# SK3000v1_-_3_FINAL.net
KiCad netlist of a schematic drawn in EAGLE
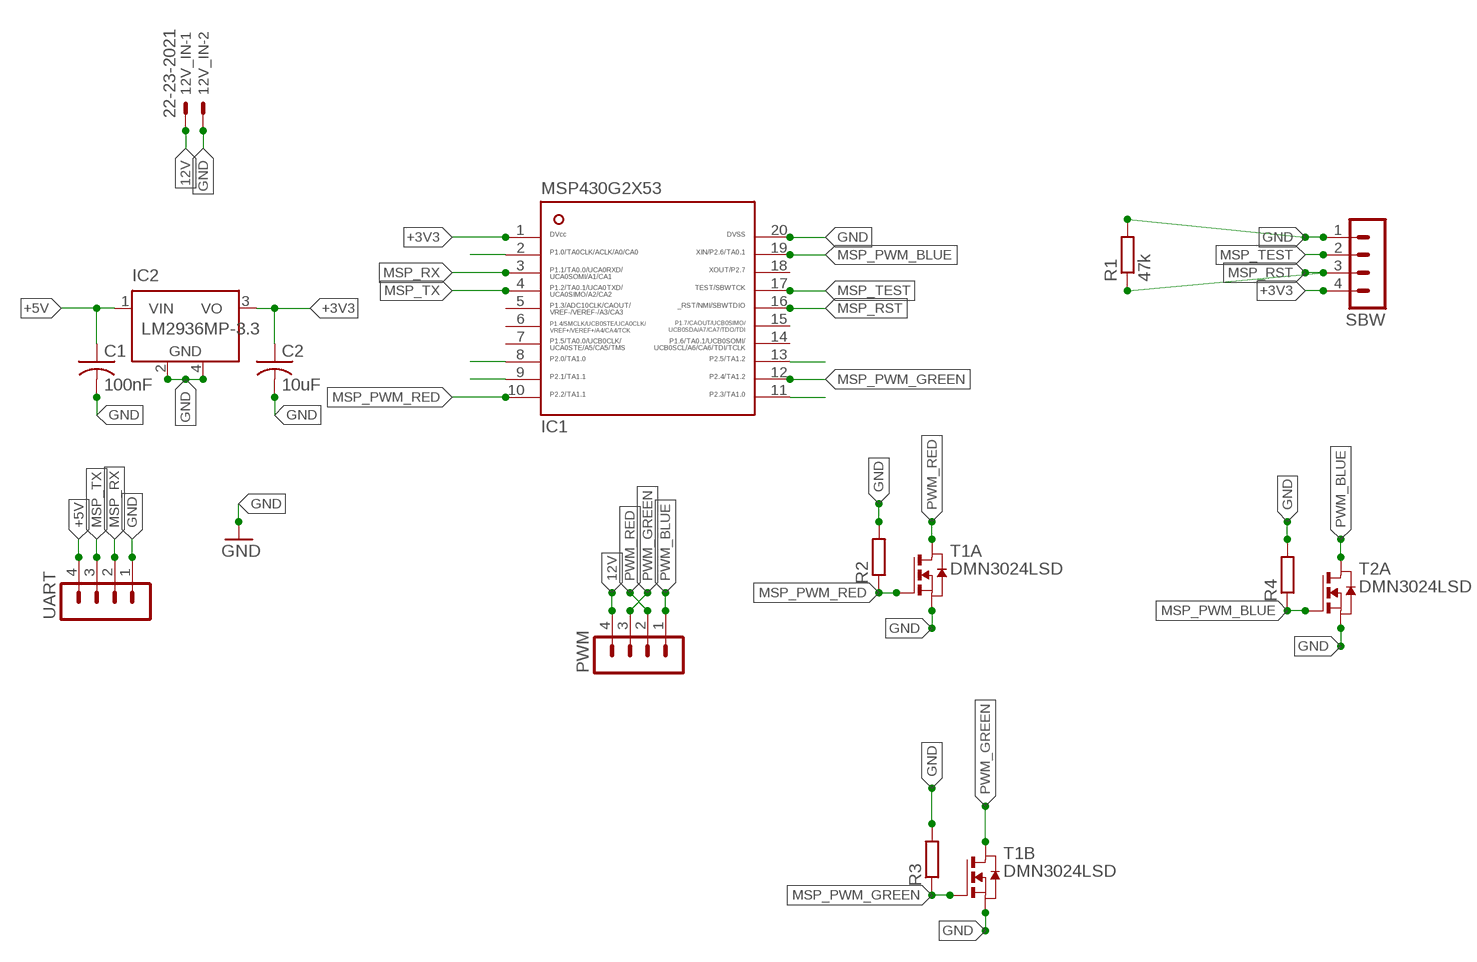
[diagram p0: schematic, sheet 1]

(export (version "E")
  (design (tool "Eeschema 10.0.6"))
  (components
    (comp (ref "12V_IN")
      (value "22-23-2021")
      (footprint "eagle-import:22-23-2021")
      (fields (field (name "MF") "MOLEX"))
      (libsource (lib "eagle-import") (part "22-23-2021"))
    )
    (comp (ref "C1")
      (value "100nF")
      (footprint "eagle-import:C025-024X044")
      (libsource (lib "eagle-import") (part "C-US025-024X044"))
    )
    (comp (ref "C2")
      (value "10uF")
      (footprint "eagle-import:C025-024X044")
      (libsource (lib "eagle-import") (part "C-US025-024X044"))
    )
    (comp (ref "IC1")
      (value "MSP430G2553")
      (footprint "eagle-import:PW20")
      (libsource (lib "eagle-import") (part "MSP430G2X53-20PW20"))
    )
    (comp (ref "IC2")
      (value "LM2936MP-3.3")
      (footprint "eagle-import:SOT223")
      (fields (field (name "MF") "NATIONAL SEMICONDUCTOR") (field (name "MPN") "LM2936MP-3.3/NOPB"))
      (libsource (lib "eagle-import") (part "LM2936MP?-3.3"))
    )
    (comp (ref "PWM")
      (value "MA04-1")
      (footprint "eagle-import:MA04-1")
      (libsource (lib "eagle-import") (part "MA04-1"))
    )
    (comp (ref "R1")
      (value "47k")
      (footprint "eagle-import:R0603")
      (libsource (lib "eagle-import") (part "R-EU_R0603"))
    )
    (comp (ref "R2")
      (value "R-EU_R0603")
      (footprint "eagle-import:R0603")
      (libsource (lib "eagle-import") (part "R-EU_R0603"))
    )
    (comp (ref "R3")
      (value "R-EU_R0603")
      (footprint "eagle-import:R0603")
      (libsource (lib "eagle-import") (part "R-EU_R0603"))
    )
    (comp (ref "R4")
      (value "R-EU_R0603")
      (footprint "eagle-import:R0603")
      (libsource (lib "eagle-import") (part "R-EU_R0603"))
    )
    (comp (ref "SBW")
      (value "MA04-1")
      (footprint "eagle-import:MA04-1")
      (libsource (lib "eagle-import") (part "MA04-1"))
    )
    (comp (ref "T1")
      (value "DMN3024LSD")
      (footprint "eagle-import:SO8")
      (libsource (lib "eagle-import") (part "DMN3024LSD"))
    )
    (comp (ref "T2")
      (value "DMN3024LSD")
      (footprint "eagle-import:SO8")
      (libsource (lib "eagle-import") (part "DMN3024LSD"))
    )
    (comp (ref "UART")
      (value "MA04-1")
      (footprint "eagle-import:MA04-1")
      (libsource (lib "eagle-import") (part "MA04-1"))
    )
  )
  (nets
    (net (code "1") (name "+3V3") (class "Default")
      (node (ref "C2") (pin "1") (pinfunction "1_1") (pintype "passive"))
      (node (ref "IC1") (pin "1") (pinfunction "1_1") (pintype "bidirectional"))
      (node (ref "IC2") (pin "3") (pinfunction "VO_3") (pintype "passive"))
      (node (ref "SBW") (pin "4") (pinfunction "4_4") (pintype "passive"))
    )
    (net (code "2") (name "+5V") (class "Default")
      (node (ref "C1") (pin "1") (pinfunction "1_1") (pintype "passive"))
      (node (ref "IC2") (pin "1") (pinfunction "VIN_1") (pintype "input"))
      (node (ref "UART") (pin "4") (pinfunction "4_4") (pintype "passive"))
    )
    (net (code "3") (name "12V") (class "Default")
      (node (ref "12V_IN") (pin "1") (pinfunction "S_1") (pintype "passive"))
      (node (ref "PWM") (pin "4") (pinfunction "4_4") (pintype "passive"))
    )
    (net (code "4") (name "GND") (class "Default")
      (node (ref "12V_IN") (pin "2") (pinfunction "S_2") (pintype "passive"))
      (node (ref "C1") (pin "2") (pinfunction "2_2") (pintype "passive"))
      (node (ref "C2") (pin "2") (pinfunction "2_2") (pintype "passive"))
      (node (ref "IC1") (pin "20") (pinfunction "20_20") (pintype "bidirectional"))
      (node (ref "IC2") (pin "2") (pinfunction "GND_2") (pintype "passive"))
      (node (ref "IC2") (pin "4") (pinfunction "GND_4") (pintype "passive"))
      (node (ref "R1") (pin "2") (pinfunction "2_2") (pintype "passive"))
      (node (ref "R2") (pin "2") (pinfunction "2_2") (pintype "passive"))
      (node (ref "R3") (pin "2") (pinfunction "2_2") (pintype "passive"))
      (node (ref "R4") (pin "2") (pinfunction "2_2") (pintype "passive"))
      (node (ref "SBW") (pin "1") (pinfunction "1_1") (pintype "passive"))
      (node (ref "T1") (pin "1") (pinfunction "S_1") (pintype "passive"))
      (node (ref "T1") (pin "3") (pinfunction "S_3") (pintype "passive"))
      (node (ref "T2") (pin "1") (pinfunction "S_1") (pintype "passive"))
      (node (ref "UART") (pin "1") (pinfunction "1_1") (pintype "passive"))
    )
    (net (code "5") (name "MSP_PWM_BLUE") (class "Default")
      (node (ref "IC1") (pin "19") (pinfunction "19_19") (pintype "bidirectional"))
      (node (ref "R4") (pin "1") (pinfunction "1_1") (pintype "passive"))
      (node (ref "T2") (pin "2") (pinfunction "G_2") (pintype "passive"))
    )
    (net (code "6") (name "MSP_PWM_GREEN") (class "Default")
      (node (ref "IC1") (pin "12") (pinfunction "12_12") (pintype "bidirectional"))
      (node (ref "R3") (pin "1") (pinfunction "1_1") (pintype "passive"))
      (node (ref "T1") (pin "4") (pinfunction "G_4") (pintype "passive"))
    )
    (net (code "7") (name "MSP_PWM_RED") (class "Default")
      (node (ref "IC1") (pin "10") (pinfunction "10_10") (pintype "bidirectional"))
      (node (ref "R2") (pin "1") (pinfunction "1_1") (pintype "passive"))
      (node (ref "T1") (pin "2") (pinfunction "G_2") (pintype "passive"))
    )
    (net (code "8") (name "MSP_RST") (class "Default")
      (node (ref "IC1") (pin "16") (pinfunction "16_16") (pintype "bidirectional"))
      (node (ref "R1") (pin "1") (pinfunction "1_1") (pintype "passive"))
      (node (ref "SBW") (pin "3") (pinfunction "3_3") (pintype "passive"))
    )
    (net (code "9") (name "MSP_RX") (class "Default")
      (node (ref "IC1") (pin "3") (pinfunction "3_3") (pintype "bidirectional"))
      (node (ref "UART") (pin "2") (pinfunction "2_2") (pintype "passive"))
    )
    (net (code "10") (name "MSP_TEST") (class "Default")
      (node (ref "IC1") (pin "17") (pinfunction "17_17") (pintype "bidirectional"))
      (node (ref "SBW") (pin "2") (pinfunction "2_2") (pintype "passive"))
    )
    (net (code "11") (name "MSP_TX") (class "Default")
      (node (ref "IC1") (pin "4") (pinfunction "4_4") (pintype "bidirectional"))
      (node (ref "UART") (pin "3") (pinfunction "3_3") (pintype "passive"))
    )
    (net (code "12") (name "PWM_BLUE") (class "Default")
      (node (ref "PWM") (pin "1") (pinfunction "1_1") (pintype "passive"))
      (node (ref "T2") (pin "7") (pinfunction "D_7") (pintype "passive"))
      (node (ref "T2") (pin "8") (pinfunction "D_8") (pintype "passive"))
    )
    (net (code "13") (name "PWM_GREEN") (class "Default")
      (node (ref "PWM") (pin "3") (pinfunction "3_3") (pintype "passive"))
      (node (ref "T1") (pin "5") (pinfunction "D_5") (pintype "passive"))
      (node (ref "T1") (pin "6") (pinfunction "D_6") (pintype "passive"))
    )
    (net (code "14") (name "PWM_RED") (class "Default")
      (node (ref "PWM") (pin "2") (pinfunction "2_2") (pintype "passive"))
      (node (ref "T1") (pin "7") (pinfunction "D_7") (pintype "passive"))
      (node (ref "T1") (pin "8") (pinfunction "D_8") (pintype "passive"))
    )
    (net (code "15") (name "unconnected-(IC1-Pad2)") (class "Default")
      (node (ref "IC1") (pin "2") (pinfunction "2_2") (pintype "bidirectional"))
    )
    (net (code "16") (name "unconnected-(IC1-Pad5)") (class "Default")
      (node (ref "IC1") (pin "5") (pinfunction "5_5") (pintype "bidirectional"))
    )
    (net (code "17") (name "unconnected-(IC1-Pad6)") (class "Default")
      (node (ref "IC1") (pin "6") (pinfunction "6_6") (pintype "bidirectional"))
    )
    (net (code "18") (name "unconnected-(IC1-Pad7)") (class "Default")
      (node (ref "IC1") (pin "7") (pinfunction "7_7") (pintype "bidirectional"))
    )
    (net (code "19") (name "unconnected-(IC1-Pad8)") (class "Default")
      (node (ref "IC1") (pin "8") (pinfunction "8_8") (pintype "bidirectional"))
    )
    (net (code "20") (name "unconnected-(IC1-Pad9)") (class "Default")
      (node (ref "IC1") (pin "9") (pinfunction "9_9") (pintype "bidirectional"))
    )
    (net (code "21") (name "unconnected-(IC1-Pad11)") (class "Default")
      (node (ref "IC1") (pin "11") (pinfunction "11_11") (pintype "bidirectional"))
    )
    (net (code "22") (name "unconnected-(IC1-Pad13)") (class "Default")
      (node (ref "IC1") (pin "13") (pinfunction "13_13") (pintype "bidirectional"))
    )
    (net (code "23") (name "unconnected-(IC1-Pad14)") (class "Default")
      (node (ref "IC1") (pin "14") (pinfunction "14_14") (pintype "bidirectional"))
    )
    (net (code "24") (name "unconnected-(IC1-Pad15)") (class "Default")
      (node (ref "IC1") (pin "15") (pinfunction "15_15") (pintype "bidirectional"))
    )
    (net (code "25") (name "unconnected-(IC1-Pad18)") (class "Default")
      (node (ref "IC1") (pin "18") (pinfunction "18_18") (pintype "bidirectional"))
    )
  )
)
